# 10_LED.net
KiCad netlist of a schematic drawn in Altium Designer
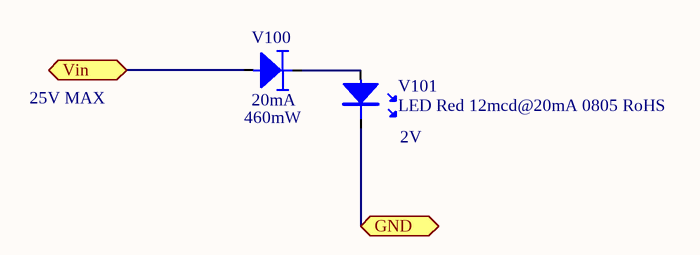
[diagram p0: 10_LED.SchDoc]

(export (version "E")
  (design (tool "Eeschema 10.0.6"))
  (components
    (comp (ref "V100")
      (value "20mA")
      (footprint "SOD123")
      (description "CURRENT REG")
      (fields (field (name "MANUFACTURER") "On Semiconductor") (field (name "PARTNUMBER") "NSI45015WT1G"))
      (libsource (lib "SVN_BOMGEN_Database_2014") (part "AL5809"))
    )
    (comp (ref "V101")
      (value "LED Red 12mcd@20mA 0805 RoHS")
      (footprint "LED-0805")
      (description "LED")
      (fields
        (field (name "MANUFACTURER") "Kingbright")
        (field (name "PARTNUMBER") "KP-2012EC")
        (field (name "CHECKEDBY") "ART")
      )
      (libsource (lib "SVN_BOMGEN_Database_2014") (part "LED"))
    )
  )
  (nets
    (net (code "1") (name "/GND") (class "Default") (node (ref "V101") (pin "k") (pintype "passive")))
    (net (code "2") (name "/Vin") (class "Default")
      (node (ref "V100") (pin "a") (pinfunction "a_a") (pintype "passive"))
    )
    (net (code "3") (name "Net-(V100-Padk)") (class "Default")
      (node (ref "V100") (pin "k") (pinfunction "k_k") (pintype "passive"))
      (node (ref "V101") (pin "a") (pintype "passive"))
    )
  )
)
